# SNR8503M_BLDC_HALL_6-80V_20A_V2_0.net
KiCad netlist of a schematic drawn in Altium Designer
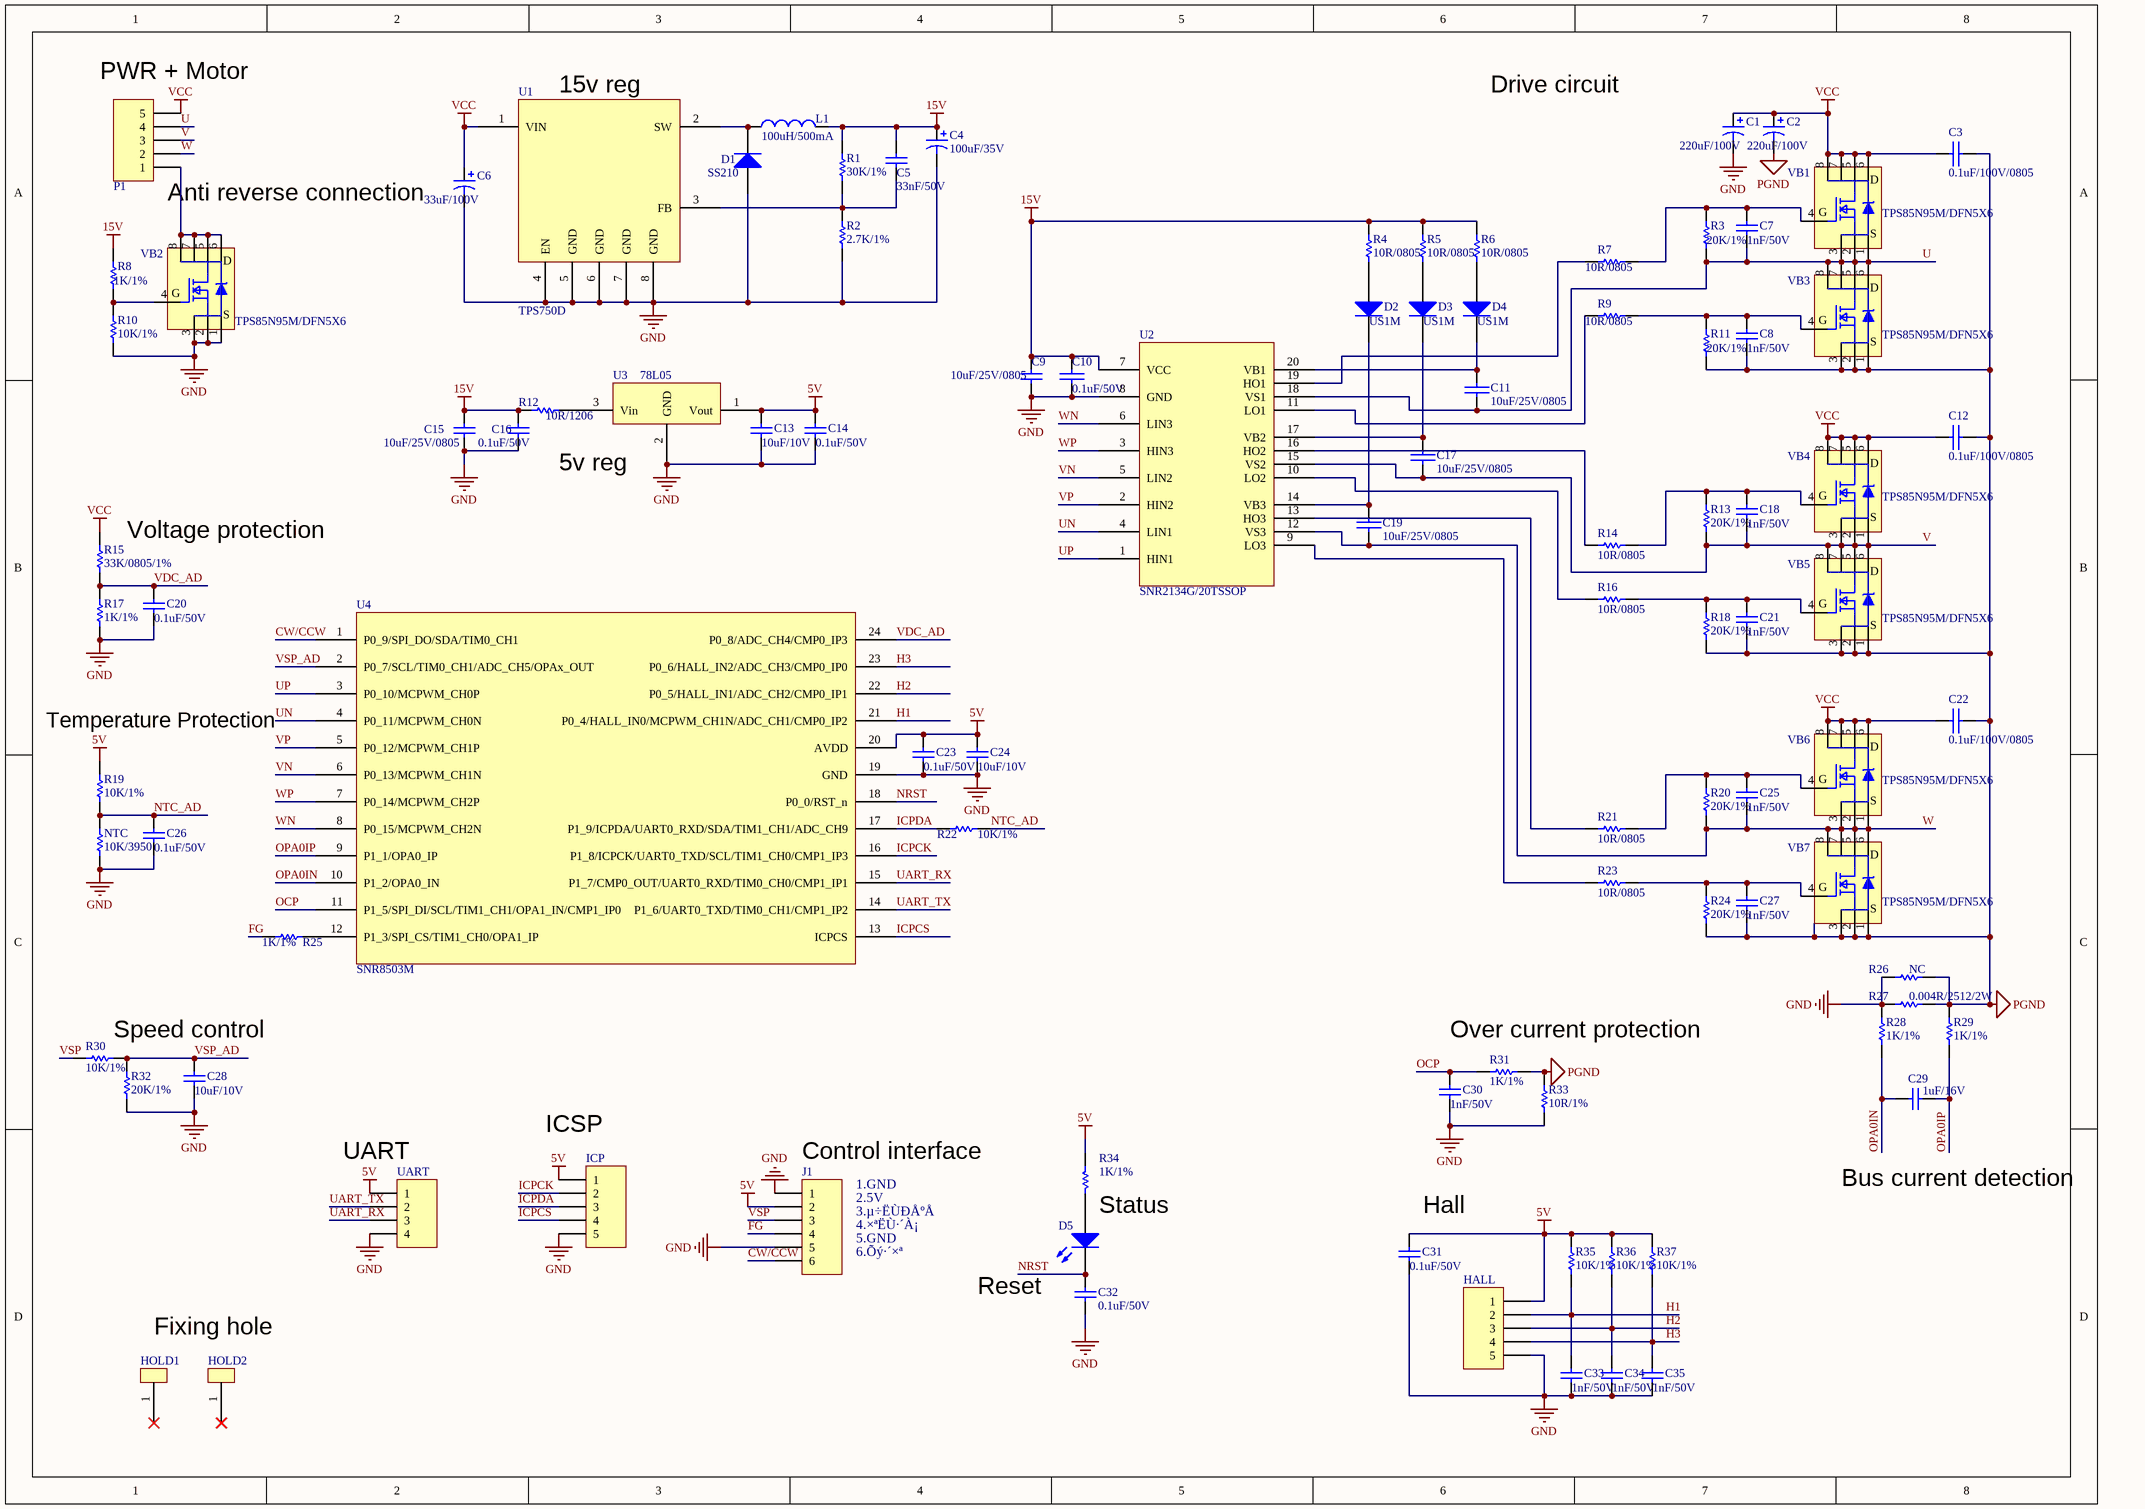
[diagram p0: SNR8503M_BLDC_HALL_6-80V_20A_V2.0.SchDoc]

(export (version "E")
  (design (tool "Eeschema 10.0.6"))
  (components
    (comp (ref "C1")
      (value "220uF/100V")
      (footprint "CAP 5.0*12.5*20")
      (description "Polarized Capacitor (Radial)")
      (fields (field (name "PUBLISHER") "Altium Limited"))
      (libsource (lib "Miscellaneous Devices") (part "Cap Pol1"))
    )
    (comp (ref "C2")
      (value "220uF/100V")
      (footprint "CAP 5.0*12.5*20")
      (description "Polarized Capacitor (Radial)")
      (fields (field (name "PUBLISHER") "Altium Limited"))
      (libsource (lib "Miscellaneous Devices") (part "Cap Pol1"))
    )
    (comp (ref "C3")
      (value "0.1uF/100V/0805")
      (footprint "C 0805_L")
      (description "Capacitor")
      (libsource (lib "*") (part "C"))
    )
    (comp (ref "C4")
      (value "100uF/35V")
      (footprint "CM D(6.3*7.7)")
      (description "Polarized Capacitor (Radial)")
      (fields (field (name "PUBLISHER") "Altium Limited"))
      (libsource (lib "Miscellaneous Devices") (part "Cap Pol1"))
    )
    (comp (ref "C5")
      (value "33nF/50V")
      (footprint "C 0603_L")
      (description "Capacitor")
      (fields (field (name "PUBLISHER") "Altium Limited"))
      (libsource (lib "Miscellaneous Devices") (part "Cap"))
    )
    (comp (ref "C6")
      (value "33uF/100V")
      (footprint "CM F(10*10.2)")
      (description "Polarized Capacitor (Radial)")
      (fields (field (name "PUBLISHER") "Altium Limited"))
      (libsource (lib "Miscellaneous Devices") (part "Cap Pol1"))
    )
    (comp (ref "C7")
      (value "1nF/50V")
      (footprint "C 0603_L")
      (description "Capacitor")
      (fields (field (name "PUBLISHER") "Altium Limited"))
      (libsource (lib "Miscellaneous Devices") (part "Cap"))
    )
    (comp (ref "C8")
      (value "1nF/50V")
      (footprint "C 0603_L")
      (description "Capacitor")
      (fields (field (name "PUBLISHER") "Altium Limited"))
      (libsource (lib "Miscellaneous Devices") (part "Cap"))
    )
    (comp (ref "C9")
      (value "10uF/25V/0805")
      (footprint "C 0805_L")
      (description "Capacitor")
      (fields (field (name "PUBLISHER") "Altium Limited"))
      (libsource (lib "Miscellaneous Devices") (part "Cap"))
    )
    (comp (ref "C10")
      (value "0.1uF/50V")
      (footprint "C 0603_L")
      (description "Capacitor")
      (libsource (lib "*") (part "C"))
    )
    (comp (ref "C11")
      (value "10uF/25V/0805")
      (footprint "C 0805_L")
      (description "Capacitor")
      (libsource (lib "*") (part "C"))
    )
    (comp (ref "C12")
      (value "0.1uF/100V/0805")
      (footprint "C 0805_L")
      (description "Capacitor")
      (libsource (lib "*") (part "C"))
    )
    (comp (ref "C13")
      (value "10uF/10V")
      (footprint "C 0603_L")
      (description "Capacitor")
      (fields (field (name "PUBLISHER") "Altium Limited"))
      (libsource (lib "Miscellaneous Devices") (part "Cap"))
    )
    (comp (ref "C14")
      (value "0.1uF/50V")
      (footprint "C 0603_L")
      (description "Capacitor")
      (fields (field (name "PUBLISHER") "Altium Limited"))
      (libsource (lib "Miscellaneous Devices") (part "Cap"))
    )
    (comp (ref "C15")
      (value "10uF/25V/0805")
      (footprint "C 0805_L")
      (description "Capacitor")
      (fields (field (name "PUBLISHER") "Altium Limited"))
      (libsource (lib "Miscellaneous Devices") (part "Cap"))
    )
    (comp (ref "C16")
      (value "0.1uF/50V")
      (footprint "C 0603_L")
      (description "Capacitor")
      (fields (field (name "PUBLISHER") "Altium Limited"))
      (libsource (lib "Miscellaneous Devices") (part "Cap"))
    )
    (comp (ref "C17")
      (value "10uF/25V/0805")
      (footprint "C 0805_L")
      (description "Capacitor")
      (libsource (lib "*") (part "C"))
    )
    (comp (ref "C18")
      (value "1nF/50V")
      (footprint "C 0603_L")
      (description "Capacitor")
      (fields (field (name "PUBLISHER") "Altium Limited"))
      (libsource (lib "Miscellaneous Devices") (part "Cap"))
    )
    (comp (ref "C19")
      (value "10uF/25V/0805")
      (footprint "C 0805_L")
      (description "Capacitor")
      (libsource (lib "*") (part "C"))
    )
    (comp (ref "C20")
      (value "0.1uF/50V")
      (footprint "C 0603_L")
      (description "Capacitor")
      (fields (field (name "PUBLISHER") "Altium Limited"))
      (libsource (lib "Miscellaneous Devices") (part "Cap"))
    )
    (comp (ref "C21")
      (value "1nF/50V")
      (footprint "C 0603_L")
      (description "Capacitor")
      (fields (field (name "PUBLISHER") "Altium Limited"))
      (libsource (lib "Miscellaneous Devices") (part "Cap"))
    )
    (comp (ref "C22")
      (value "0.1uF/100V/0805")
      (footprint "C 0805_L")
      (description "Capacitor")
      (libsource (lib "*") (part "C"))
    )
    (comp (ref "C23")
      (value "0.1uF/50V")
      (footprint "C 0603_L")
      (description "Capacitor")
      (fields (field (name "PUBLISHER") "Altium Limited"))
      (libsource (lib "Miscellaneous Devices") (part "Cap"))
    )
    (comp (ref "C24")
      (value "10uF/10V")
      (footprint "C 0603_L")
      (description "Capacitor")
      (fields (field (name "PUBLISHER") "Altium Limited"))
      (libsource (lib "Miscellaneous Devices") (part "Cap"))
    )
    (comp (ref "C25")
      (value "1nF/50V")
      (footprint "C 0603_L")
      (description "Capacitor")
      (fields (field (name "PUBLISHER") "Altium Limited"))
      (libsource (lib "Miscellaneous Devices") (part "Cap"))
    )
    (comp (ref "C26")
      (value "0.1uF/50V")
      (footprint "C 0603_L")
      (description "Capacitor")
      (fields (field (name "PUBLISHER") "Altium Limited"))
      (libsource (lib "Miscellaneous Devices") (part "Cap"))
    )
    (comp (ref "C27")
      (value "1nF/50V")
      (footprint "C 0603_L")
      (description "Capacitor")
      (fields (field (name "PUBLISHER") "Altium Limited"))
      (libsource (lib "Miscellaneous Devices") (part "Cap"))
    )
    (comp (ref "C28")
      (value "10uF/10V")
      (footprint "C 0603_L")
      (description "Capacitor")
      (fields (field (name "PUBLISHER") "Altium Limited"))
      (libsource (lib "Miscellaneous Devices") (part "Cap"))
    )
    (comp (ref "C29")
      (value "1uF/16V")
      (footprint "C 0603_L")
      (description "Capacitor")
      (fields (field (name "PUBLISHER") "Altium Limited"))
      (libsource (lib "Miscellaneous Devices") (part "Cap"))
    )
    (comp (ref "C30")
      (value "1nF/50V")
      (footprint "C 0603_L")
      (description "Capacitor")
      (fields (field (name "PUBLISHER") "Altium Limited"))
      (libsource (lib "Miscellaneous Devices") (part "Cap"))
    )
    (comp (ref "C31")
      (value "0.1uF/50V")
      (footprint "C 0603_L")
      (description "Capacitor")
      (fields (field (name "PUBLISHER") "Altium Limited"))
      (libsource (lib "Miscellaneous Devices") (part "Cap"))
    )
    (comp (ref "C32")
      (value "0.1uF/50V")
      (footprint "C 0603_L")
      (description "Capacitor")
      (fields (field (name "PUBLISHER") "Altium Limited"))
      (libsource (lib "Miscellaneous Devices") (part "Cap"))
    )
    (comp (ref "C33")
      (value "1nF/50V")
      (footprint "C 0603_L")
      (description "Capacitor")
      (fields (field (name "PUBLISHER") "Altium Limited"))
      (libsource (lib "Miscellaneous Devices") (part "Cap"))
    )
    (comp (ref "C34")
      (value "1nF/50V")
      (footprint "C 0603_L")
      (description "Capacitor")
      (fields (field (name "PUBLISHER") "Altium Limited"))
      (libsource (lib "Miscellaneous Devices") (part "Cap"))
    )
    (comp (ref "C35")
      (value "1nF/50V")
      (footprint "C 0603_L")
      (description "Capacitor")
      (fields (field (name "PUBLISHER") "Altium Limited"))
      (libsource (lib "Miscellaneous Devices") (part "Cap"))
    )
    (comp (ref "D1")
      (value "SS210")
      (footprint "SMA")
      (description "Default Diode")
      (fields (field (name "PUBLISHER") "Altium Limited"))
      (libsource (lib "Miscellaneous Devices") (part "Diode"))
    )
    (comp (ref "D2")
      (value "US1M")
      (footprint "SOD-123")
      (description "Default Diode")
      (fields (field (name "PUBLISHER") "Altium Limited"))
      (libsource (lib "Miscellaneous Devices") (part "Diode"))
    )
    (comp (ref "D3")
      (value "US1M")
      (footprint "SOD-123")
      (description "Default Diode")
      (fields (field (name "PUBLISHER") "Altium Limited"))
      (libsource (lib "Miscellaneous Devices") (part "Diode"))
    )
    (comp (ref "D4")
      (value "US1M")
      (footprint "SOD-123")
      (description "Default Diode")
      (fields (field (name "PUBLISHER") "Altium Limited"))
      (libsource (lib "Miscellaneous Devices") (part "Diode"))
    )
    (comp (ref "D5")
      (value "LED0")
      (footprint "LED 0805R")
      (description "Typical INFRARED GaAs LED")
      (fields (field (name "PUBLISHER") "Altium Limited"))
      (libsource (lib "Miscellaneous Devices") (part "LED0"))
    )
    (comp (ref "HALL")
      (value "Header 5")
      (footprint "HDR2.54-LI-5P")
      (description "Header, 5-Pin")
      (fields (field (name "PUBLISHER") "Altium Limited"))
      (libsource (lib "") (part "Header 5_2"))
    )
    (comp (ref "HOLD1")
      (value "TEST POINT")
      (footprint "HOLD330-600")
      (libsource (lib "SNANER—SCH库") (part "TEST POINT"))
    )
    (comp (ref "HOLD2")
      (value "TEST POINT")
      (footprint "HOLD330-600")
      (libsource (lib "SNANER—SCH库") (part "TEST POINT"))
    )
    (comp (ref "ICP")
      (value "ICP")
      (footprint "HDR2.54-LI-5P")
      (description "Header, 5-Pin")
      (fields (field (name "PUBLISHER") "Altium Limited"))
      (libsource (lib "Miscellaneous Connectors") (part "Header 5"))
    )
    (comp (ref "J1")
      (value "J1")
      (footprint "HDR2.54-LI-6P")
      (description "Header, 6-Pin")
      (fields (field (name "PUBLISHER") "Altium Limited"))
      (libsource (lib "Miscellaneous Connectors") (part "Header 6"))
    )
    (comp (ref "L1")
      (value "100uH/500mA")
      (footprint "NR5020")
      (description "Inductor")
      (fields (field (name "PUBLISHER") "Altium Limited"))
      (libsource (lib "Miscellaneous Devices") (part "Inductor"))
    )
    (comp (ref "NTC")
      (value "10K/3950")
      (footprint "R 0603_L")
      (description "Resistor")
      (fields (field (name "PUBLISHER") "Altium Limited"))
      (libsource (lib "Miscellaneous Devices") (part "Res1"))
    )
    (comp (ref "P1")
      (value "P1")
      (footprint "CONN-TH-5.08-5P")
      (description "Header, 5-Pin")
      (fields (field (name "PUBLISHER") "Altium Limited"))
      (libsource (lib "") (part "Header 5_1"))
    )
    (comp (ref "R1")
      (value "30K/1%")
      (footprint "R 0603_L")
      (description "Resistor")
      (fields (field (name "PUBLISHER") "Altium Limited"))
      (libsource (lib "Miscellaneous Devices") (part "Res1"))
    )
    (comp (ref "R2")
      (value "2.7K/1%")
      (footprint "R 0603_L")
      (description "Resistor")
      (fields (field (name "PUBLISHER") "Altium Limited"))
      (libsource (lib "Miscellaneous Devices") (part "Res1"))
    )
    (comp (ref "R3")
      (value "20K/1%")
      (footprint "R 0603_L")
      (description "Resistor")
      (fields (field (name "PUBLISHER") "Altium Limited"))
      (libsource (lib "Miscellaneous Devices") (part "Res1"))
    )
    (comp (ref "R4")
      (value "10R/0805")
      (footprint "R 0805_L")
      (description "Resistor")
      (fields (field (name "PUBLISHER") "Altium Limited"))
      (libsource (lib "Miscellaneous Devices") (part "Res1"))
    )
    (comp (ref "R5")
      (value "10R/0805")
      (footprint "R 0805_L")
      (description "Resistor")
      (fields (field (name "PUBLISHER") "Altium Limited"))
      (libsource (lib "Miscellaneous Devices") (part "Res1"))
    )
    (comp (ref "R6")
      (value "10R/0805")
      (footprint "R 0805_L")
      (description "Resistor")
      (fields (field (name "PUBLISHER") "Altium Limited"))
      (libsource (lib "Miscellaneous Devices") (part "Res1"))
    )
    (comp (ref "R7")
      (value "10R/0805")
      (footprint "R 0805_L")
      (description "Resistor")
      (fields (field (name "PUBLISHER") "Altium Limited"))
      (libsource (lib "Miscellaneous Devices") (part "Res1"))
    )
    (comp (ref "R8")
      (value "1K/1%")
      (footprint "R 0603_L")
      (description "Resistor")
      (fields (field (name "PUBLISHER") "Altium Limited"))
      (libsource (lib "Miscellaneous Devices") (part "Res1"))
    )
    (comp (ref "R9")
      (value "10R/0805")
      (footprint "R 0805_L")
      (description "Resistor")
      (fields (field (name "PUBLISHER") "Altium Limited"))
      (libsource (lib "Miscellaneous Devices") (part "Res1"))
    )
    (comp (ref "R10")
      (value "10K/1%")
      (footprint "R 0603_L")
      (description "Resistor")
      (fields (field (name "PUBLISHER") "Altium Limited"))
      (libsource (lib "Miscellaneous Devices") (part "Res1"))
    )
    (comp (ref "R11")
      (value "20K/1%")
      (footprint "R 0603_L")
      (description "Resistor")
      (fields (field (name "PUBLISHER") "Altium Limited"))
      (libsource (lib "Miscellaneous Devices") (part "Res1"))
    )
    (comp (ref "R12")
      (value "10R/1206")
      (footprint "R 1206_L")
      (description "Resistor")
      (fields (field (name "PUBLISHER") "Altium Limited"))
      (libsource (lib "Miscellaneous Devices") (part "Res1"))
    )
    (comp (ref "R13")
      (value "20K/1%")
      (footprint "R 0603_L")
      (description "Resistor")
      (fields (field (name "PUBLISHER") "Altium Limited"))
      (libsource (lib "Miscellaneous Devices") (part "Res1"))
    )
    (comp (ref "R14")
      (value "10R/0805")
      (footprint "R 0805_L")
      (description "Resistor")
      (fields (field (name "PUBLISHER") "Altium Limited"))
      (libsource (lib "Miscellaneous Devices") (part "Res1"))
    )
    (comp (ref "R15")
      (value "33K/0805/1%")
      (footprint "R 0805_L")
      (description "Resistor")
      (fields (field (name "PUBLISHER") "Altium Limited"))
      (libsource (lib "Miscellaneous Devices") (part "Res1"))
    )
    (comp (ref "R16")
      (value "10R/0805")
      (footprint "R 0805_L")
      (description "Resistor")
      (fields (field (name "PUBLISHER") "Altium Limited"))
      (libsource (lib "Miscellaneous Devices") (part "Res1"))
    )
    (comp (ref "R17")
      (value "1K/1%")
      (footprint "R 0603_L")
      (description "Resistor")
      (fields (field (name "PUBLISHER") "Altium Limited"))
      (libsource (lib "Miscellaneous Devices") (part "Res1"))
    )
    (comp (ref "R18")
      (value "20K/1%")
      (footprint "R 0603_L")
      (description "Resistor")
      (fields (field (name "PUBLISHER") "Altium Limited"))
      (libsource (lib "Miscellaneous Devices") (part "Res1"))
    )
    (comp (ref "R19")
      (value "10K/1%")
      (footprint "R 0603_L")
      (description "Resistor")
      (fields (field (name "PUBLISHER") "Altium Limited"))
      (libsource (lib "Miscellaneous Devices") (part "Res1"))
    )
    (comp (ref "R20")
      (value "20K/1%")
      (footprint "R 0603_L")
      (description "Resistor")
      (fields (field (name "PUBLISHER") "Altium Limited"))
      (libsource (lib "Miscellaneous Devices") (part "Res1"))
    )
    (comp (ref "R21")
      (value "10R/0805")
      (footprint "R 0805_L")
      (description "Resistor")
      (fields (field (name "PUBLISHER") "Altium Limited"))
      (libsource (lib "Miscellaneous Devices") (part "Res1"))
    )
    (comp (ref "R22")
      (value "10K/1%")
      (footprint "R 0603_L")
      (description "Resistor")
      (fields (field (name "PUBLISHER") "Altium Limited"))
      (libsource (lib "Miscellaneous Devices") (part "Res1"))
    )
    (comp (ref "R23")
      (value "10R/0805")
      (footprint "R 0805_L")
      (description "Resistor")
      (fields (field (name "PUBLISHER") "Altium Limited"))
      (libsource (lib "Miscellaneous Devices") (part "Res1"))
    )
    (comp (ref "R24")
      (value "20K/1%")
      (footprint "R 0603_L")
      (description "Resistor")
      (fields (field (name "PUBLISHER") "Altium Limited"))
      (libsource (lib "Miscellaneous Devices") (part "Res1"))
    )
    (comp (ref "R25")
      (value "1K/1%")
      (footprint "R 0603_L")
      (description "Resistor")
      (fields (field (name "PUBLISHER") "Altium Limited"))
      (libsource (lib "Miscellaneous Devices") (part "Res1"))
    )
    (comp (ref "R26")
      (value "NC")
      (footprint "R 2512_L")
      (description "Resistor")
      (fields (field (name "PUBLISHER") "Altium Limited"))
      (libsource (lib "Miscellaneous Devices") (part "Res1"))
    )
    (comp (ref "R27")
      (value "0.004R/2512/2W")
      (footprint "R 2512_L")
      (description "Resistor")
      (fields (field (name "PUBLISHER") "Altium Limited"))
      (libsource (lib "Miscellaneous Devices") (part "Res1"))
    )
    (comp (ref "R28")
      (value "1K/1%")
      (footprint "R 0603_L")
      (description "Resistor")
      (fields (field (name "PUBLISHER") "Altium Limited"))
      (libsource (lib "Miscellaneous Devices") (part "Res1"))
    )
    (comp (ref "R29")
      (value "1K/1%")
      (footprint "R 0603_L")
      (description "Resistor")
      (fields (field (name "PUBLISHER") "Altium Limited"))
      (libsource (lib "Miscellaneous Devices") (part "Res1"))
    )
    (comp (ref "R30")
      (value "10K/1%")
      (footprint "R 0603_L")
      (description "Resistor")
      (fields (field (name "PUBLISHER") "Altium Limited"))
      (libsource (lib "Miscellaneous Devices") (part "Res1"))
    )
    (comp (ref "R31")
      (value "1K/1%")
      (footprint "R 0603_L")
      (description "Resistor")
      (fields (field (name "PUBLISHER") "Altium Limited"))
      (libsource (lib "Miscellaneous Devices") (part "Res1"))
    )
    (comp (ref "R32")
      (value "20K/1%")
      (footprint "R 0603_L")
      (description "Resistor")
      (fields (field (name "PUBLISHER") "Altium Limited"))
      (libsource (lib "Miscellaneous Devices") (part "Res1"))
    )
    (comp (ref "R33")
      (value "10R/1%")
      (footprint "R 0603_L")
      (description "Resistor")
      (fields (field (name "PUBLISHER") "Altium Limited"))
      (libsource (lib "Miscellaneous Devices") (part "Res1"))
    )
    (comp (ref "R34")
      (value "1K/1%")
      (footprint "R 0603_L")
      (description "Resistor")
      (fields (field (name "PUBLISHER") "Altium Limited"))
      (libsource (lib "Miscellaneous Devices") (part "Res1"))
    )
    (comp (ref "R35")
      (value "10K/1%")
      (footprint "R 0603_L")
      (description "Resistor")
      (fields (field (name "PUBLISHER") "Altium Limited"))
      (libsource (lib "Miscellaneous Devices") (part "Res1"))
    )
    (comp (ref "R36")
      (value "10K/1%")
      (footprint "R 0603_L")
      (description "Resistor")
      (fields (field (name "PUBLISHER") "Altium Limited"))
      (libsource (lib "Miscellaneous Devices") (part "Res1"))
    )
    (comp (ref "R37")
      (value "10K/1%")
      (footprint "R 0603_L")
      (description "Resistor")
      (fields (field (name "PUBLISHER") "Altium Limited"))
      (libsource (lib "Miscellaneous Devices") (part "Res1"))
    )
    (comp (ref "U1")
      (value "TPS750D")
      (footprint "SOIC-8_EP")
      (libsource (lib "SNANER—SCH库") (part "TPS750D"))
    )
    (comp (ref "U2")
      (value "SNR2134G/20TSSOP")
      (footprint "TSSOP20_L")
      (libsource (lib "SNANER—SCH库") (part "SNR2134G"))
    )
    (comp (ref "U3") (value "78L05") (footprint "SOT89_L") (libsource (lib "SNANER—SCH库") (part "78L05")))
    (comp (ref "U4")
      (value "SNR8503M")
      (footprint "SSOP-24_150mil")
      (libsource (lib "SNANER—SCH库") (part "SNR8503M_1"))
    )
    (comp (ref "UART")
      (value "UART")
      (footprint "HDR2.54-LI-4P")
      (description "Header, 4-Pin")
      (fields (field (name "PUBLISHER") "Altium Limited"))
      (libsource (lib "Miscellaneous Connectors") (part "Header 4"))
    )
    (comp (ref "VB1")
      (value "TPS85N95M/DFN5X6")
      (footprint "DFN5x6-8L_TPS")
      (description "MOS")
      (libsource (lib "SNANER—SCH库") (part "MOSFET8-A"))
    )
    (comp (ref "VB2")
      (value "TPS85N95M/DFN5X6")
      (footprint "DFN5x6-8L_TPS")
      (description "MOS")
      (libsource (lib "SNANER—SCH库") (part "MOSFET8-A"))
    )
    (comp (ref "VB3")
      (value "TPS85N95M/DFN5X6")
      (footprint "DFN5x6-8L_TPS")
      (description "MOS")
      (libsource (lib "SNANER—SCH库") (part "MOSFET8-A"))
    )
    (comp (ref "VB4")
      (value "TPS85N95M/DFN5X6")
      (footprint "DFN5x6-8L_TPS")
      (description "MOS")
      (libsource (lib "SNANER—SCH库") (part "MOSFET8-A"))
    )
    (comp (ref "VB5")
      (value "TPS85N95M/DFN5X6")
      (footprint "DFN5x6-8L_TPS")
      (description "MOS")
      (libsource (lib "SNANER—SCH库") (part "MOSFET8-A"))
    )
    (comp (ref "VB6")
      (value "TPS85N95M/DFN5X6")
      (footprint "DFN5x6-8L_TPS")
      (description "MOS")
      (libsource (lib "SNANER—SCH库") (part "MOSFET8-A"))
    )
    (comp (ref "VB7")
      (value "TPS85N95M/DFN5X6")
      (footprint "DFN5x6-8L_TPS")
      (description "MOS")
      (libsource (lib "SNANER—SCH库") (part "MOSFET8-A"))
    )
  )
  (nets
    (net (code "5") (name "/CW{slash}CCW") (class "Default")
      (node (ref "J1") (pin "6") (pinfunction "6_6") (pintype "passive"))
      (node (ref "U4") (pin "1") (pinfunction "P0_9/SPI_DO/SDA/TIM0_CH1_1") (pintype "passive"))
    )
    (net (code "8") (name "/FG") (class "Default")
      (node (ref "J1") (pin "4") (pinfunction "4_4") (pintype "passive"))
      (node (ref "R25") (pin "2") (pinfunction "2_2") (pintype "passive"))
    )
    (net (code "10") (name "/H1") (class "Default")
      (node (ref "C33") (pin "2") (pinfunction "2_2") (pintype "passive"))
      (node (ref "HALL") (pin "2") (pinfunction "2_2") (pintype "passive"))
      (node (ref "R35") (pin "1") (pinfunction "1_1") (pintype "passive"))
      (node (ref "U4") (pin "21") (pinfunction "P0_4/HALL_IN0/MCPWM_CH1N/ADC_CH1/CMP0_IP2_21") (pintype "passive"))
    )
    (net (code "11") (name "/H2") (class "Default")
      (node (ref "C34") (pin "2") (pinfunction "2_2") (pintype "passive"))
      (node (ref "HALL") (pin "3") (pinfunction "3_3") (pintype "passive"))
      (node (ref "R36") (pin "1") (pinfunction "1_1") (pintype "passive"))
      (node (ref "U4") (pin "22") (pinfunction "P0_5/HALL_IN1/ADC_CH2/CMP0_IP1_22") (pintype "passive"))
    )
    (net (code "12") (name "/H3") (class "Default")
      (node (ref "C35") (pin "2") (pinfunction "2_2") (pintype "passive"))
      (node (ref "HALL") (pin "4") (pinfunction "4_4") (pintype "passive"))
      (node (ref "R37") (pin "1") (pinfunction "1_1") (pintype "passive"))
      (node (ref "U4") (pin "23") (pinfunction "P0_6/HALL_IN2/ADC_CH3/CMP0_IP0_23") (pintype "passive"))
    )
    (net (code "14") (name "/ICPCK") (class "Default")
      (node (ref "ICP") (pin "2") (pinfunction "2_2") (pintype "passive"))
      (node (ref "U4") (pin "16") (pinfunction "P1_8/ICPCK/UART0_TXD/SCL/TIM1_CH0/CMP1_IP3_16") (pintype "passive"))
    )
    (net (code "15") (name "/ICPCS") (class "Default")
      (node (ref "ICP") (pin "4") (pinfunction "4_4") (pintype "passive"))
      (node (ref "U4") (pin "13") (pinfunction "ICPCS_13") (pintype "passive"))
    )
    (net (code "16") (name "/ICPDA") (class "Default")
      (node (ref "ICP") (pin "3") (pinfunction "3_3") (pintype "passive"))
      (node (ref "R22") (pin "2") (pinfunction "2_2") (pintype "passive"))
      (node (ref "U4") (pin "17") (pinfunction "P1_9/ICPDA/UART0_RXD/SDA/TIM1_CH1/ADC_CH9_17") (pintype "passive"))
    )
    (net (code "18") (name "/NRST") (class "Default")
      (node (ref "C32") (pin "2") (pinfunction "2_2") (pintype "passive"))
      (node (ref "D5") (pin "2") (pinfunction "K_2") (pintype "passive"))
      (node (ref "U4") (pin "18") (pinfunction "P0_0/RST_n_18") (pintype "passive"))
    )
    (net (code "19") (name "/NTC_AD") (class "Default")
      (node (ref "C26") (pin "2") (pinfunction "2_2") (pintype "passive"))
      (node (ref "NTC") (pin "2") (pinfunction "2_2") (pintype "passive"))
      (node (ref "R19") (pin "1") (pinfunction "1_1") (pintype "passive"))
      (node (ref "R22") (pin "1") (pinfunction "1_1") (pintype "passive"))
    )
    (net (code "20") (name "/OCP") (class "Default")
      (node (ref "C30") (pin "2") (pinfunction "2_2") (pintype "passive"))
      (node (ref "R31") (pin "1") (pinfunction "1_1") (pintype "passive"))
      (node (ref "U4") (pin "11") (pinfunction "P1_5/SPI_DI/SCL/TIM1_CH1/OPA1_IN/CMP1_IP0_11") (pintype "passive"))
    )
    (net (code "21") (name "/OPA0IN") (class "Default")
      (node (ref "C29") (pin "2") (pinfunction "2_2") (pintype "passive"))
      (node (ref "R28") (pin "2") (pinfunction "2_2") (pintype "passive"))
      (node (ref "U4") (pin "10") (pinfunction "P1_2/OPA0_IN_10") (pintype "passive"))
    )
    (net (code "22") (name "/OPA0IP") (class "Default")
      (node (ref "C29") (pin "1") (pinfunction "1_1") (pintype "passive"))
      (node (ref "R29") (pin "2") (pinfunction "2_2") (pintype "passive"))
      (node (ref "U4") (pin "9") (pinfunction "P1_1/OPA0_IP_9") (pintype "passive"))
    )
    (net (code "29") (name "/U") (class "Default")
      (node (ref "C11") (pin "2") (pinfunction "2_2") (pintype "passive"))
      (node (ref "C7") (pin "1") (pinfunction "1_1") (pintype "passive"))
      (node (ref "P1") (pin "4") (pinfunction "4_4") (pintype "passive"))
      (node (ref "R3") (pin "2") (pinfunction "2_2") (pintype "passive"))
      (node (ref "U2") (pin "18") (pinfunction "VS1_18") (pintype "passive"))
      (node (ref "VB1") (pin "1") (pinfunction "S_1") (pintype "passive"))
      (node (ref "VB1") (pin "2") (pinfunction "S_2") (pintype "passive"))
      (node (ref "VB1") (pin "3") (pinfunction "S_3") (pintype "passive"))
      (node (ref "VB3") (pin "5") (pinfunction "D_5") (pintype "passive"))
      (node (ref "VB3") (pin "6") (pinfunction "D_6") (pintype "passive"))
      (node (ref "VB3") (pin "7") (pinfunction "D_7") (pintype "passive"))
      (node (ref "VB3") (pin "8") (pinfunction "D_8") (pintype "passive"))
    )
    (net (code "31") (name "/UART_RX") (class "Default")
      (node (ref "U4") (pin "15") (pinfunction "P1_7/CMP0_OUT/UART0_RXD/TIM0_CH0/CMP1_IP1_15") (pintype "passive"))
      (node (ref "UART") (pin "3") (pinfunction "3_3") (pintype "passive"))
    )
    (net (code "32") (name "/UART_TX") (class "Default")
      (node (ref "U4") (pin "14") (pinfunction "P1_6/UART0_TXD/TIM0_CH1/CMP1_IP2_14") (pintype "passive"))
      (node (ref "UART") (pin "2") (pinfunction "2_2") (pintype "passive"))
    )
    (net (code "33") (name "/UN") (class "Default")
      (node (ref "U2") (pin "4") (pinfunction "LIN1_4") (pintype "passive"))
      (node (ref "U4") (pin "4") (pinfunction "P0_11/MCPWM_CH0N_4") (pintype "passive"))
    )
    (net (code "34") (name "/UP") (class "Default")
      (node (ref "U2") (pin "1") (pinfunction "HIN1_1") (pintype "passive"))
      (node (ref "U4") (pin "3") (pinfunction "P0_10/MCPWM_CH0P_3") (pintype "passive"))
    )
    (net (code "35") (name "/V") (class "Default")
      (node (ref "C17") (pin "2") (pinfunction "2_2") (pintype "passive"))
      (node (ref "C18") (pin "1") (pinfunction "1_1") (pintype "passive"))
      (node (ref "P1") (pin "3") (pinfunction "3_3") (pintype "passive"))
      (node (ref "R13") (pin "2") (pinfunction "2_2") (pintype "passive"))
      (node (ref "U2") (pin "15") (pinfunction "VS2_15") (pintype "passive"))
      (node (ref "VB4") (pin "1") (pinfunction "S_1") (pintype "passive"))
      (node (ref "VB4") (pin "2") (pinfunction "S_2") (pintype "passive"))
      (node (ref "VB4") (pin "3") (pinfunction "S_3") (pintype "passive"))
      (node (ref "VB5") (pin "5") (pinfunction "D_5") (pintype "passive"))
      (node (ref "VB5") (pin "6") (pinfunction "D_6") (pintype "passive"))
      (node (ref "VB5") (pin "7") (pinfunction "D_7") (pintype "passive"))
      (node (ref "VB5") (pin "8") (pinfunction "D_8") (pintype "passive"))
    )
    (net (code "36") (name "/VDC_AD") (class "Default")
      (node (ref "C20") (pin "2") (pinfunction "2_2") (pintype "passive"))
      (node (ref "R15") (pin "1") (pinfunction "1_1") (pintype "passive"))
      (node (ref "R17") (pin "2") (pinfunction "2_2") (pintype "passive"))
      (node (ref "U4") (pin "24") (pinfunction "P0_8/ADC_CH4/CMP0_IP3_24") (pintype "passive"))
    )
    (net (code "37") (name "/VN") (class "Default")
      (node (ref "U2") (pin "5") (pinfunction "LIN2_5") (pintype "passive"))
      (node (ref "U4") (pin "6") (pinfunction "P0_13/MCPWM_CH1N_6") (pintype "passive"))
    )
    (net (code "38") (name "/VP") (class "Default")
      (node (ref "U2") (pin "2") (pinfunction "HIN2_2") (pintype "passive"))
      (node (ref "U4") (pin "5") (pinfunction "P0_12/MCPWM_CH1P_5") (pintype "passive"))
    )
    (net (code "39") (name "/VSP") (class "Default")
      (node (ref "J1") (pin "3") (pinfunction "3_3") (pintype "passive"))
      (node (ref "R30") (pin "2") (pinfunction "2_2") (pintype "passive"))
    )
    (net (code "40") (name "/VSP_AD") (class "Default")
      (node (ref "C28") (pin "2") (pinfunction "2_2") (pintype "passive"))
      (node (ref "R30") (pin "1") (pinfunction "1_1") (pintype "passive"))
      (node (ref "R32") (pin "1") (pinfunction "1_1") (pintype "passive"))
      (node (ref "U4") (pin "2") (pinfunction "P0_7/SCL/TIM0_CH1/ADC_CH5/OPAx_OUT_2") (pintype "passive"))
    )
    (net (code "42") (name "/W") (class "Default")
      (node (ref "C19") (pin "2") (pinfunction "2_2") (pintype "passive"))
      (node (ref "C25") (pin "1") (pinfunction "1_1") (pintype "passive"))
      (node (ref "P1") (pin "2") (pinfunction "2_2") (pintype "passive"))
      (node (ref "R20") (pin "2") (pinfunction "2_2") (pintype "passive"))
      (node (ref "U2") (pin "12") (pinfunction "VS3_12") (pintype "passive"))
      (node (ref "VB6") (pin "1") (pinfunction "S_1") (pintype "passive"))
      (node (ref "VB6") (pin "2") (pinfunction "S_2") (pintype "passive"))
      (node (ref "VB6") (pin "3") (pinfunction "S_3") (pintype "passive"))
      (node (ref "VB7") (pin "5") (pinfunction "D_5") (pintype "passive"))
      (node (ref "VB7") (pin "6") (pinfunction "D_6") (pintype "passive"))
      (node (ref "VB7") (pin "7") (pinfunction "D_7") (pintype "passive"))
      (node (ref "VB7") (pin "8") (pinfunction "D_8") (pintype "passive"))
    )
    (net (code "43") (name "/WN") (class "Default")
      (node (ref "U2") (pin "6") (pinfunction "LIN3_6") (pintype "passive"))
      (node (ref "U4") (pin "8") (pinfunction "P0_15/MCPWM_CH2N_8") (pintype "passive"))
    )
    (net (code "44") (name "/WP") (class "Default")
      (node (ref "U2") (pin "3") (pinfunction "HIN3_3") (pintype "passive"))
      (node (ref "U4") (pin "7") (pinfunction "P0_14/MCPWM_CH2P_7") (pintype "passive"))
    )
    (net (code "45") (name "5V") (class "Default")
      (node (ref "C13") (pin "2") (pinfunction "2_2") (pintype "passive"))
      (node (ref "C14") (pin "2") (pinfunction "2_2") (pintype "passive"))
      (node (ref "C23") (pin "2") (pinfunction "2_2") (pintype "passive"))
      (node (ref "C24") (pin "2") (pinfunction "2_2") (pintype "passive"))
      (node (ref "C31") (pin "2") (pinfunction "2_2") (pintype "passive"))
      (node (ref "HALL") (pin "1") (pinfunction "1_1") (pintype "passive"))
      (node (ref "ICP") (pin "1") (pinfunction "1_1") (pintype "passive"))
      (node (ref "J1") (pin "2") (pinfunction "2_2") (pintype "passive"))
      (node (ref "R19") (pin "2") (pinfunction "2_2") (pintype "passive"))
      (node (ref "R34") (pin "2") (pinfunction "2_2") (pintype "passive"))
      (node (ref "R35") (pin "2") (pinfunction "2_2") (pintype "passive"))
      (node (ref "R36") (pin "2") (pinfunction "2_2") (pintype "passive"))
      (node (ref "R37") (pin "2") (pinfunction "2_2") (pintype "passive"))
      (node (ref "U3") (pin "1") (pinfunction "Vout_1") (pintype "passive"))
      (node (ref "U4") (pin "20") (pinfunction "AVDD_20") (pintype "passive"))
      (node (ref "UART") (pin "1") (pinfunction "1_1") (pintype "passive"))
    )
    (net (code "46") (name "15V") (class "Default")
      (node (ref "C10") (pin "2") (pinfunction "2_2") (pintype "passive"))
      (node (ref "C15") (pin "2") (pinfunction "2_2") (pintype "passive"))
      (node (ref "C16") (pin "2") (pinfunction "2_2") (pintype "passive"))
      (node (ref "C4") (pin "1") (pinfunction "1_1") (pintype "passive"))
      (node (ref "C5") (pin "2") (pinfunction "2_2") (pintype "passive"))
      (node (ref "C9") (pin "2") (pinfunction "2_2") (pintype "passive"))
      (node (ref "L1") (pin "2") (pinfunction "2_2") (pintype "passive"))
      (node (ref "R1") (pin "1") (pinfunction "1_1") (pintype "passive"))
      (node (ref "R12") (pin "2") (pinfunction "2_2") (pintype "passive"))
      (node (ref "R4") (pin "1") (pinfunction "1_1") (pintype "passive"))
      (node (ref "R5") (pin "1") (pinfunction "1_1") (pintype "passive"))
      (node (ref "R6") (pin "1") (pinfunction "1_1") (pintype "passive"))
      (node (ref "R8") (pin "2") (pinfunction "2_2") (pintype "passive"))
      (node (ref "U2") (pin "7") (pinfunction "VCC_7") (pintype "passive"))
    )
    (net (code "47") (name "GND") (class "Default")
      (node (ref "C1") (pin "2") (pinfunction "2_2") (pintype "passive"))
      (node (ref "C10") (pin "1") (pinfunction "1_1") (pintype "passive"))
      (node (ref "C13") (pin "1") (pinfunction "1_1") (pintype "passive"))
      (node (ref "C14") (pin "1") (pinfunction "1_1") (pintype "passive"))
      (node (ref "C15") (pin "1") (pinfunction "1_1") (pintype "passive"))
      (node (ref "C16") (pin "1") (pinfunction "1_1") (pintype "passive"))
      (node (ref "C20") (pin "1") (pinfunction "1_1") (pintype "passive"))
      (node (ref "C23") (pin "1") (pinfunction "1_1") (pintype "passive"))
      (node (ref "C24") (pin "1") (pinfunction "1_1") (pintype "passive"))
      (node (ref "C26") (pin "1") (pinfunction "1_1") (pintype "passive"))
      (node (ref "C28") (pin "1") (pinfunction "1_1") (pintype "passive"))
      (node (ref "C30") (pin "1") (pinfunction "1_1") (pintype "passive"))
      (node (ref "C31") (pin "1") (pinfunction "1_1") (pintype "passive"))
      (node (ref "C32") (pin "1") (pinfunction "1_1") (pintype "passive"))
      (node (ref "C33") (pin "1") (pinfunction "1_1") (pintype "passive"))
      (node (ref "C34") (pin "1") (pinfunction "1_1") (pintype "passive"))
      (node (ref "C35") (pin "1") (pinfunction "1_1") (pintype "passive"))
      (node (ref "C4") (pin "2") (pinfunction "2_2") (pintype "passive"))
      (node (ref "C6") (pin "2") (pinfunction "2_2") (pintype "passive"))
      (node (ref "C9") (pin "1") (pinfunction "1_1") (pintype "passive"))
      (node (ref "D1") (pin "1") (pinfunction "A_1") (pintype "passive"))
      (node (ref "HALL") (pin "5") (pinfunction "5_5") (pintype "passive"))
      (node (ref "ICP") (pin "5") (pinfunction "5_5") (pintype "passive"))
      (node (ref "J1") (pin "1") (pinfunction "1_1") (pintype "passive"))
      (node (ref "J1") (pin "5") (pinfunction "5_5") (pintype "passive"))
      (node (ref "NTC") (pin "1") (pinfunction "1_1") (pintype "passive"))
      (node (ref "R10") (pin "1") (pinfunction "1_1") (pintype "passive"))
      (node (ref "R17") (pin "1") (pinfunction "1_1") (pintype "passive"))
      (node (ref "R2") (pin "2") (pinfunction "2_2") (pintype "passive"))
      (node (ref "R26") (pin "1") (pinfunction "1_1") (pintype "passive"))
      (node (ref "R27") (pin "1") (pinfunction "1_1") (pintype "passive"))
      (node (ref "R28") (pin "1") (pinfunction "1_1") (pintype "passive"))
      (node (ref "R32") (pin "2") (pinfunction "2_2") (pintype "passive"))
      (node (ref "R33") (pin "2") (pinfunction "2_2") (pintype "passive"))
      (node (ref "U1") (pin "4") (pinfunction "EN_4") (pintype "passive"))
      (node (ref "U1") (pin "5") (pinfunction "GND_5") (pintype "passive"))
      (node (ref "U1") (pin "6") (pinfunction "GND_6") (pintype "passive"))
      (node (ref "U1") (pin "7") (pinfunction "GND_7") (pintype "passive"))
      (node (ref "U1") (pin "8") (pinfunction "GND_8") (pintype "passive"))
      (node (ref "U2") (pin "8") (pinfunction "GND_8") (pintype "passive"))
      (node (ref "U3") (pin "2") (pinfunction "GND_2") (pintype "passive"))
      (node (ref "U4") (pin "19") (pinfunction "GND_19") (pintype "passive"))
      (node (ref "UART") (pin "4") (pinfunction "4_4") (pintype "passive"))
      (node (ref "VB2") (pin "1") (pinfunction "S_1") (pintype "passive"))
      (node (ref "VB2") (pin "2") (pinfunction "S_2") (pintype "passive"))
      (node (ref "VB2") (pin "3") (pinfunction "S_3") (pintype "passive"))
    )
    (net (code "48") (name "Net-(D1-K)") (class "Default")
      (node (ref "D1") (pin "2") (pinfunction "K_2") (pintype "passive"))
      (node (ref "L1") (pin "1") (pinfunction "1_1") (pintype "passive"))
      (node (ref "U1") (pin "2") (pinfunction "SW_2") (pintype "passive"))
    )
    (net (code "49") (name "Net-(D2-A)") (class "Default")
      (node (ref "D2") (pin "1") (pinfunction "A_1") (pintype "passive"))
      (node (ref "R4") (pin "2") (pinfunction "2_2") (pintype "passive"))
    )
    (net (code "50") (name "Net-(D2-K)") (class "Default")
      (node (ref "C19") (pin "1") (pinfunction "1_1") (pintype "passive"))
      (node (ref "D2") (pin "2") (pinfunction "K_2") (pintype "passive"))
      (node (ref "U2") (pin "14") (pinfunction "VB3_14") (pintype "passive"))
    )
    (net (code "51") (name "Net-(D3-A)") (class "Default")
      (node (ref "D3") (pin "1") (pinfunction "A_1") (pintype "passive"))
      (node (ref "R5") (pin "2") (pinfunction "2_2") (pintype "passive"))
    )
    (net (code "52") (name "Net-(D3-K)") (class "Default")
      (node (ref "C17") (pin "1") (pinfunction "1_1") (pintype "passive"))
      (node (ref "D3") (pin "2") (pinfunction "K_2") (pintype "passive"))
      (node (ref "U2") (pin "17") (pinfunction "VB2_17") (pintype "passive"))
    )
    (net (code "53") (name "Net-(D4-A)") (class "Default")
      (node (ref "D4") (pin "1") (pinfunction "A_1") (pintype "passive"))
      (node (ref "R6") (pin "2") (pinfunction "2_2") (pintype "passive"))
    )
    (net (code "54") (name "Net-(D4-K)") (class "Default")
      (node (ref "C11") (pin "1") (pinfunction "1_1") (pintype "passive"))
      (node (ref "D4") (pin "2") (pinfunction "K_2") (pintype "passive"))
      (node (ref "U2") (pin "20") (pinfunction "VB1_20") (pintype "passive"))
    )
    (net (code "55") (name "Net-(D5-A)") (class "Default")
      (node (ref "D5") (pin "1") (pinfunction "A_1") (pintype "passive"))
      (node (ref "R34") (pin "1") (pinfunction "1_1") (pintype "passive"))
    )
    (net (code "56") (name "Net-(P1-Pad1)") (class "Default")
      (node (ref "P1") (pin "1") (pinfunction "1_1") (pintype "passive"))
      (node (ref "VB2") (pin "5") (pinfunction "D_5") (pintype "passive"))
      (node (ref "VB2") (pin "6") (pinfunction "D_6") (pintype "passive"))
      (node (ref "VB2") (pin "7") (pinfunction "D_7") (pintype "passive"))
      (node (ref "VB2") (pin "8") (pinfunction "D_8") (pintype "passive"))
    )
    (net (code "57") (name "Net-(U1-FB)") (class "Default")
      (node (ref "C5") (pin "1") (pinfunction "1_1") (pintype "passive"))
      (node (ref "R1") (pin "2") (pinfunction "2_2") (pintype "passive"))
      (node (ref "R2") (pin "1") (pinfunction "1_1") (pintype "passive"))
      (node (ref "U1") (pin "3") (pinfunction "FB_3") (pintype "passive"))
    )
    (net (code "58") (name "Net-(U2-HO1)") (class "Default")
      (node (ref "R7") (pin "2") (pinfunction "2_2") (pintype "passive"))
      (node (ref "U2") (pin "19") (pinfunction "HO1_19") (pintype "passive"))
    )
    (net (code "59") (name "Net-(U2-HO2)") (class "Default")
      (node (ref "R14") (pin "2") (pinfunction "2_2") (pintype "passive"))
      (node (ref "U2") (pin "16") (pinfunction "HO2_16") (pintype "passive"))
    )
    (net (code "60") (name "Net-(U2-HO3)") (class "Default")
      (node (ref "R21") (pin "2") (pinfunction "2_2") (pintype "passive"))
      (node (ref "U2") (pin "13") (pinfunction "HO3_13") (pintype "passive"))
    )
    (net (code "61") (name "Net-(U2-LO1)") (class "Default")
      (node (ref "R9") (pin "2") (pinfunction "2_2") (pintype "passive"))
      (node (ref "U2") (pin "11") (pinfunction "LO1_11") (pintype "passive"))
    )
    (net (code "62") (name "Net-(U2-LO2)") (class "Default")
      (node (ref "R16") (pin "2") (pinfunction "2_2") (pintype "passive"))
      (node (ref "U2") (pin "10") (pinfunction "LO2_10") (pintype "passive"))
    )
    (net (code "63") (name "Net-(U2-LO3)") (class "Default")
      (node (ref "R23") (pin "2") (pinfunction "2_2") (pintype "passive"))
      (node (ref "U2") (pin "9") (pinfunction "LO3_9") (pintype "passive"))
    )
    (net (code "64") (name "Net-(U3-Vin)") (class "Default")
      (node (ref "R12") (pin "1") (pinfunction "1_1") (pintype "passive"))
      (node (ref "U3") (pin "3") (pinfunction "Vin_3") (pintype "passive"))
    )
    (net (code "65") (name "Net-(U4-P1_3{slash}SPI_CS{slash}TIM1_CH0{slash}OPA1_IP)") (class "Default")
      (node (ref "R25") (pin "1") (pinfunction "1_1") (pintype "passive"))
      (node (ref "U4") (pin "12") (pinfunction "P1_3/SPI_CS/TIM1_CH0/OPA1_IP_12") (pintype "passive"))
    )
    (net (code "66") (name "Net-(VB1-G)") (class "Default")
      (node (ref "C7") (pin "2") (pinfunction "2_2") (pintype "passive"))
      (node (ref "R3") (pin "1") (pinfunction "1_1") (pintype "passive"))
      (node (ref "R7") (pin "1") (pinfunction "1_1") (pintype "passive"))
      (node (ref "VB1") (pin "4") (pinfunction "G_4") (pintype "passive"))
    )
    (net (code "67") (name "Net-(VB2-G)") (class "Default")
      (node (ref "R10") (pin "2") (pinfunction "2_2") (pintype "passive"))
      (node (ref "R8") (pin "1") (pinfunction "1_1") (pintype "passive"))
      (node (ref "VB2") (pin "4") (pinfunction "G_4") (pintype "passive"))
    )
    (net (code "68") (name "Net-(VB3-G)") (class "Default")
      (node (ref "C8") (pin "2") (pinfunction "2_2") (pintype "passive"))
      (node (ref "R11") (pin "1") (pinfunction "1_1") (pintype "passive"))
      (node (ref "R9") (pin "1") (pinfunction "1_1") (pintype "passive"))
      (node (ref "VB3") (pin "4") (pinfunction "G_4") (pintype "passive"))
    )
    (net (code "69") (name "Net-(VB4-G)") (class "Default")
      (node (ref "C18") (pin "2") (pinfunction "2_2") (pintype "passive"))
      (node (ref "R13") (pin "1") (pinfunction "1_1") (pintype "passive"))
      (node (ref "R14") (pin "1") (pinfunction "1_1") (pintype "passive"))
      (node (ref "VB4") (pin "4") (pinfunction "G_4") (pintype "passive"))
    )
    (net (code "70") (name "Net-(VB5-G)") (class "Default")
      (node (ref "C21") (pin "2") (pinfunction "2_2") (pintype "passive"))
      (node (ref "R16") (pin "1") (pinfunction "1_1") (pintype "passive"))
      (node (ref "R18") (pin "1") (pinfunction "1_1") (pintype "passive"))
      (node (ref "VB5") (pin "4") (pinfunction "G_4") (pintype "passive"))
    )
    (net (code "71") (name "Net-(VB6-G)") (class "Default")
      (node (ref "C25") (pin "2") (pinfunction "2_2") (pintype "passive"))
      (node (ref "R20") (pin "1") (pinfunction "1_1") (pintype "passive"))
      (node (ref "R21") (pin "1") (pinfunction "1_1") (pintype "passive"))
      (node (ref "VB6") (pin "4") (pinfunction "G_4") (pintype "passive"))
    )
    (net (code "72") (name "Net-(VB7-G)") (class "Default")
      (node (ref "C27") (pin "2") (pinfunction "2_2") (pintype "passive"))
      (node (ref "R23") (pin "1") (pinfunction "1_1") (pintype "passive"))
      (node (ref "R24") (pin "1") (pinfunction "1_1") (pintype "passive"))
      (node (ref "VB7") (pin "4") (pinfunction "G_4") (pintype "passive"))
    )
    (net (code "73") (name "PGND") (class "Default")
      (node (ref "C12") (pin "1") (pinfunction "1_1") (pintype "passive"))
      (node (ref "C2") (pin "2") (pinfunction "2_2") (pintype "passive"))
      (node (ref "C21") (pin "1") (pinfunction "1_1") (pintype "passive"))
      (node (ref "C22") (pin "1") (pinfunction "1_1") (pintype "passive"))
      (node (ref "C27") (pin "1") (pinfunction "1_1") (pintype "passive"))
      (node (ref "C3") (pin "1") (pinfunction "1_1") (pintype "passive"))
      (node (ref "C8") (pin "1") (pinfunction "1_1") (pintype "passive"))
      (node (ref "R11") (pin "2") (pinfunction "2_2") (pintype "passive"))
      (node (ref "R18") (pin "2") (pinfunction "2_2") (pintype "passive"))
      (node (ref "R24") (pin "2") (pinfunction "2_2") (pintype "passive"))
      (node (ref "R26") (pin "2") (pinfunction "2_2") (pintype "passive"))
      (node (ref "R27") (pin "2") (pinfunction "2_2") (pintype "passive"))
      (node (ref "R29") (pin "1") (pinfunction "1_1") (pintype "passive"))
      (node (ref "R31") (pin "2") (pinfunction "2_2") (pintype "passive"))
      (node (ref "R33") (pin "1") (pinfunction "1_1") (pintype "passive"))
      (node (ref "VB3") (pin "1") (pinfunction "S_1") (pintype "passive"))
      (node (ref "VB3") (pin "2") (pinfunction "S_2") (pintype "passive"))
      (node (ref "VB3") (pin "3") (pinfunction "S_3") (pintype "passive"))
      (node (ref "VB5") (pin "1") (pinfunction "S_1") (pintype "passive"))
      (node (ref "VB5") (pin "2") (pinfunction "S_2") (pintype "passive"))
      (node (ref "VB5") (pin "3") (pinfunction "S_3") (pintype "passive"))
      (node (ref "VB7") (pin "1") (pinfunction "S_1") (pintype "passive"))
      (node (ref "VB7") (pin "2") (pinfunction "S_2") (pintype "passive"))
      (node (ref "VB7") (pin "3") (pinfunction "S_3") (pintype "passive"))
    )
    (net (code "74") (name "VCC") (class "Default")
      (node (ref "C1") (pin "1") (pinfunction "1_1") (pintype "passive"))
      (node (ref "C12") (pin "2") (pinfunction "2_2") (pintype "passive"))
      (node (ref "C2") (pin "1") (pinfunction "1_1") (pintype "passive"))
      (node (ref "C22") (pin "2") (pinfunction "2_2") (pintype "passive"))
      (node (ref "C3") (pin "2") (pinfunction "2_2") (pintype "passive"))
      (node (ref "C6") (pin "1") (pinfunction "1_1") (pintype "passive"))
      (node (ref "P1") (pin "5") (pinfunction "5_5") (pintype "passive"))
      (node (ref "R15") (pin "2") (pinfunction "2_2") (pintype "passive"))
      (node (ref "U1") (pin "1") (pinfunction "VIN_1") (pintype "passive"))
      (node (ref "VB1") (pin "5") (pinfunction "D_5") (pintype "passive"))
      (node (ref "VB1") (pin "6") (pinfunction "D_6") (pintype "passive"))
      (node (ref "VB1") (pin "7") (pinfunction "D_7") (pintype "passive"))
      (node (ref "VB1") (pin "8") (pinfunction "D_8") (pintype "passive"))
      (node (ref "VB4") (pin "5") (pinfunction "D_5") (pintype "passive"))
      (node (ref "VB4") (pin "6") (pinfunction "D_6") (pintype "passive"))
      (node (ref "VB4") (pin "7") (pinfunction "D_7") (pintype "passive"))
      (node (ref "VB4") (pin "8") (pinfunction "D_8") (pintype "passive"))
      (node (ref "VB6") (pin "5") (pinfunction "D_5") (pintype "passive"))
      (node (ref "VB6") (pin "6") (pinfunction "D_6") (pintype "passive"))
      (node (ref "VB6") (pin "7") (pinfunction "D_7") (pintype "passive"))
      (node (ref "VB6") (pin "8") (pinfunction "D_8") (pintype "passive"))
    )
    (net (code "75") (name "unconnected-(HOLD1-VOUT-Pad1)") (class "Default")
      (node (ref "HOLD1") (pin "1") (pinfunction "VOUT_1") (pintype "passive+no_connect"))
    )
    (net (code "76") (name "unconnected-(HOLD2-VOUT-Pad1)") (class "Default")
      (node (ref "HOLD2") (pin "1") (pinfunction "VOUT_1") (pintype "passive+no_connect"))
    )
  )
)
